# Sch_mcu_brd_sensors.net
KiCad netlist of a schematic drawn in Altium Designer
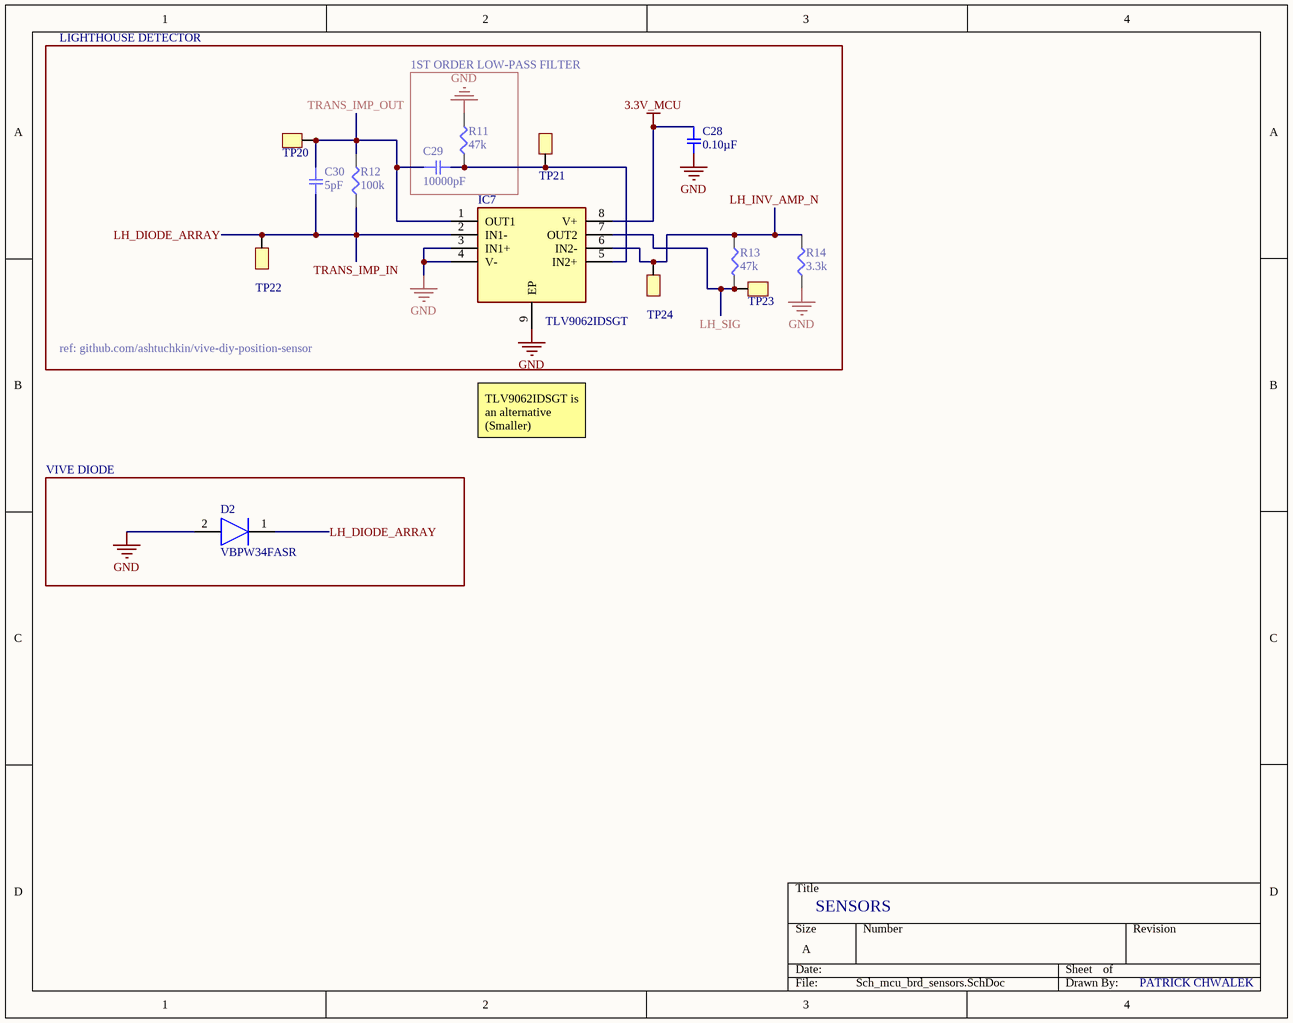
[diagram p0: Sch_mcu_brd_sensors.SchDoc]

(export (version "E")
  (design (tool "Eeschema 10.0.6"))
  (components
    (comp (ref "C28")
      (value "0.10µF")
      (footprint "SMD-0402C")
      (description "CAP CER 0.1UF 16V X7R 0402")
      (fields
        (field (name "DIGI-KEY PART NUMBER") "490-4759-1-ND")
        (field (name "PART NUMBER") "GCM155R71C104KA55D")
      )
      (libsource (lib "capacitor_murata_0402") (part "GCM155R71C104KA55D"))
    )
    (comp (ref "C29")
      (value "10000pF")
      (footprint "SMD-0402C")
      (description "CAP CER 10000PF 50V X7R 0402")
      (fields
        (field (name "DIGI-KEY PART NUMBER") "490-4762-1-ND")
        (field (name "PART NUMBER") "GCM155R71H103KA55D")
      )
      (libsource (lib "capacitor_murata_0402") (part "GCM155R71H103KA55D"))
    )
    (comp (ref "C30")
      (value "5pF")
      (footprint "SMD-0402C")
      (description "CAP CER 5PF 50V NP0 0402")
      (fields
        (field (name "DIGI-KEY PART NUMBER") "490-8103-1-ND")
        (field (name "PART NUMBER") "GJM1555C1H5R0BB01D")
      )
      (libsource (lib "capacitor_murata_0402") (part "GJM1555C1H5R0BB01D"))
    )
    (comp (ref "D2")
      (value "VBPW34FASR")
      (footprint "SamacSys:VBPW34FASR")
      (description "Diode")
      (fields (field (name "MOUSER PART NUMBER") "782-VBPW34FASR") (field (name "RS PART NUMBER") "7689401"))
      (libsource (lib "SamacSys") (part "VBPW34FASR"))
    )
    (comp (ref "IC7")
      (value "TLV9062IDSGT")
      (footprint "SamacSys:SON50P200X200X80-9N")
      (description "Integrated Circuit")
      (fields (field (name "MOUSER PART NUMBER") "595-TLV9062IDSGT"))
      (libsource (lib "SamacSys") (part "TLV9062IDSGT"))
    )
    (comp (ref "R11")
      (value "47k")
      (footprint "SMD-0402-RES")
      (description "RES SMD 47K OHM 5% 1/10W 0402")
      (fields (field (name "PART NUMBER") "ERJ-2GEJ473X") (field (name "DIGI-KEY PART NUMBER") "P47KJCT-ND"))
      (libsource (lib "Panasonic_ERJ_0402") (part "ERJ-2GEJ473X"))
    )
    (comp (ref "R12")
      (value "100k")
      (footprint "SMD-0402-RES")
      (description "RES SMD 100K OHM 5% 1/10W 0402")
      (fields (field (name "PART NUMBER") "ERJ-2GEJ104X") (field (name "DIGI-KEY PART NUMBER") "P100KJCT-ND"))
      (libsource (lib "Panasonic_ERJ_0402") (part "ERJ-2GEJ104X"))
    )
    (comp (ref "R13")
      (value "47k")
      (footprint "SMD-0402-RES")
      (description "RES SMD 47K OHM 5% 1/10W 0402")
      (fields (field (name "PART NUMBER") "ERJ-2GEJ473X") (field (name "DIGI-KEY PART NUMBER") "P47KJCT-ND"))
      (libsource (lib "Panasonic_ERJ_0402") (part "ERJ-2GEJ473X"))
    )
    (comp (ref "R14")
      (value "3.3k")
      (footprint "SMD-0402-RES")
      (description "RES SMD 3.3K OHM 5% 1/10W 0402")
      (fields (field (name "PART NUMBER") "ERJ-2GEJ332X") (field (name "DIGI-KEY PART NUMBER") "P3.3KJCT-ND"))
      (libsource (lib "Panasonic_ERJ_0402") (part "ERJ-2GEJ332X"))
    )
    (comp (ref "TP20")
      (value "TestPoint")
      (footprint "TestPoint_0.4mm")
      (libsource (lib "schematic_components") (part "TestPoint"))
    )
    (comp (ref "TP21")
      (value "TestPoint")
      (footprint "TestPoint_0.4mm")
      (libsource (lib "") (part "TestPoint_3"))
    )
    (comp (ref "TP22")
      (value "TestPoint")
      (footprint "TestPoint_0.4mm")
      (libsource (lib "") (part "TestPoint_1"))
    )
    (comp (ref "TP23")
      (value "TestPoint")
      (footprint "TestPoint_0.4mm")
      (libsource (lib "") (part "TestPoint_2"))
    )
    (comp (ref "TP24")
      (value "TestPoint")
      (footprint "TestPoint_0.4mm")
      (libsource (lib "") (part "TestPoint_1"))
    )
  )
  (nets
    (net (code "1") (name "/LH_DIODE_ARRAY") (class "Default")
      (node (ref "C30") (pin "2") (pinfunction "2_2") (pintype "passive"))
      (node (ref "D2") (pin "1") (pinfunction "A_1") (pintype "passive"))
      (node (ref "IC7") (pin "2") (pinfunction "IN1-_2") (pintype "passive"))
      (node (ref "R12") (pin "1") (pinfunction "1_1") (pintype "passive"))
      (node (ref "TP22") (pin "1") (pinfunction "1_1") (pintype "passive"))
    )
    (net (code "2") (name "/LH_INV_AMP_N") (class "Default")
      (node (ref "IC7") (pin "6") (pinfunction "IN2-_6") (pintype "passive"))
      (node (ref "R13") (pin "1") (pinfunction "1_1") (pintype "passive"))
      (node (ref "R14") (pin "2") (pinfunction "2_2") (pintype "passive"))
      (node (ref "TP24") (pin "1") (pinfunction "1_1") (pintype "passive"))
    )
    (net (code "3") (name "/LH_SIG") (class "Default")
      (node (ref "IC7") (pin "7") (pinfunction "OUT2_7") (pintype "passive"))
      (node (ref "R13") (pin "2") (pinfunction "2_2") (pintype "passive"))
      (node (ref "TP23") (pin "1") (pinfunction "1_1") (pintype "passive"))
    )
    (net (code "4") (name "/TRANS_IMP_OUT") (class "Default")
      (node (ref "C29") (pin "1") (pinfunction "1_1") (pintype "passive"))
      (node (ref "C30") (pin "1") (pinfunction "1_1") (pintype "passive"))
      (node (ref "IC7") (pin "1") (pinfunction "OUT1_1") (pintype "passive"))
      (node (ref "R12") (pin "2") (pinfunction "2_2") (pintype "passive"))
      (node (ref "TP20") (pin "1") (pinfunction "1_1") (pintype "passive"))
    )
    (net (code "5") (name "3.3V_MCU") (class "Default")
      (node (ref "C28") (pin "1") (pinfunction "1_1") (pintype "passive"))
      (node (ref "IC7") (pin "8") (pinfunction "V+_8") (pintype "passive"))
    )
    (net (code "6") (name "GND") (class "Default")
      (node (ref "C28") (pin "2") (pinfunction "2_2") (pintype "passive"))
      (node (ref "D2") (pin "2") (pinfunction "K_2") (pintype "passive"))
      (node (ref "IC7") (pin "3") (pinfunction "IN1+_3") (pintype "passive"))
      (node (ref "IC7") (pin "4") (pinfunction "V-_4") (pintype "passive"))
      (node (ref "IC7") (pin "9") (pinfunction "EP_9") (pintype "passive"))
      (node (ref "R11") (pin "2") (pinfunction "2_2") (pintype "passive"))
      (node (ref "R14") (pin "1") (pinfunction "1_1") (pintype "passive"))
    )
    (net (code "7") (name "Net-(IC7-IN2+)") (class "Default")
      (node (ref "C29") (pin "2") (pinfunction "2_2") (pintype "passive"))
      (node (ref "IC7") (pin "5") (pinfunction "IN2+_5") (pintype "passive"))
      (node (ref "R11") (pin "1") (pinfunction "1_1") (pintype "passive"))
      (node (ref "TP21") (pin "1") (pinfunction "1_1") (pintype "passive"))
    )
  )
)
